# ADC-ADC.net
KiCad netlist of a schematic drawn in Altium Designer
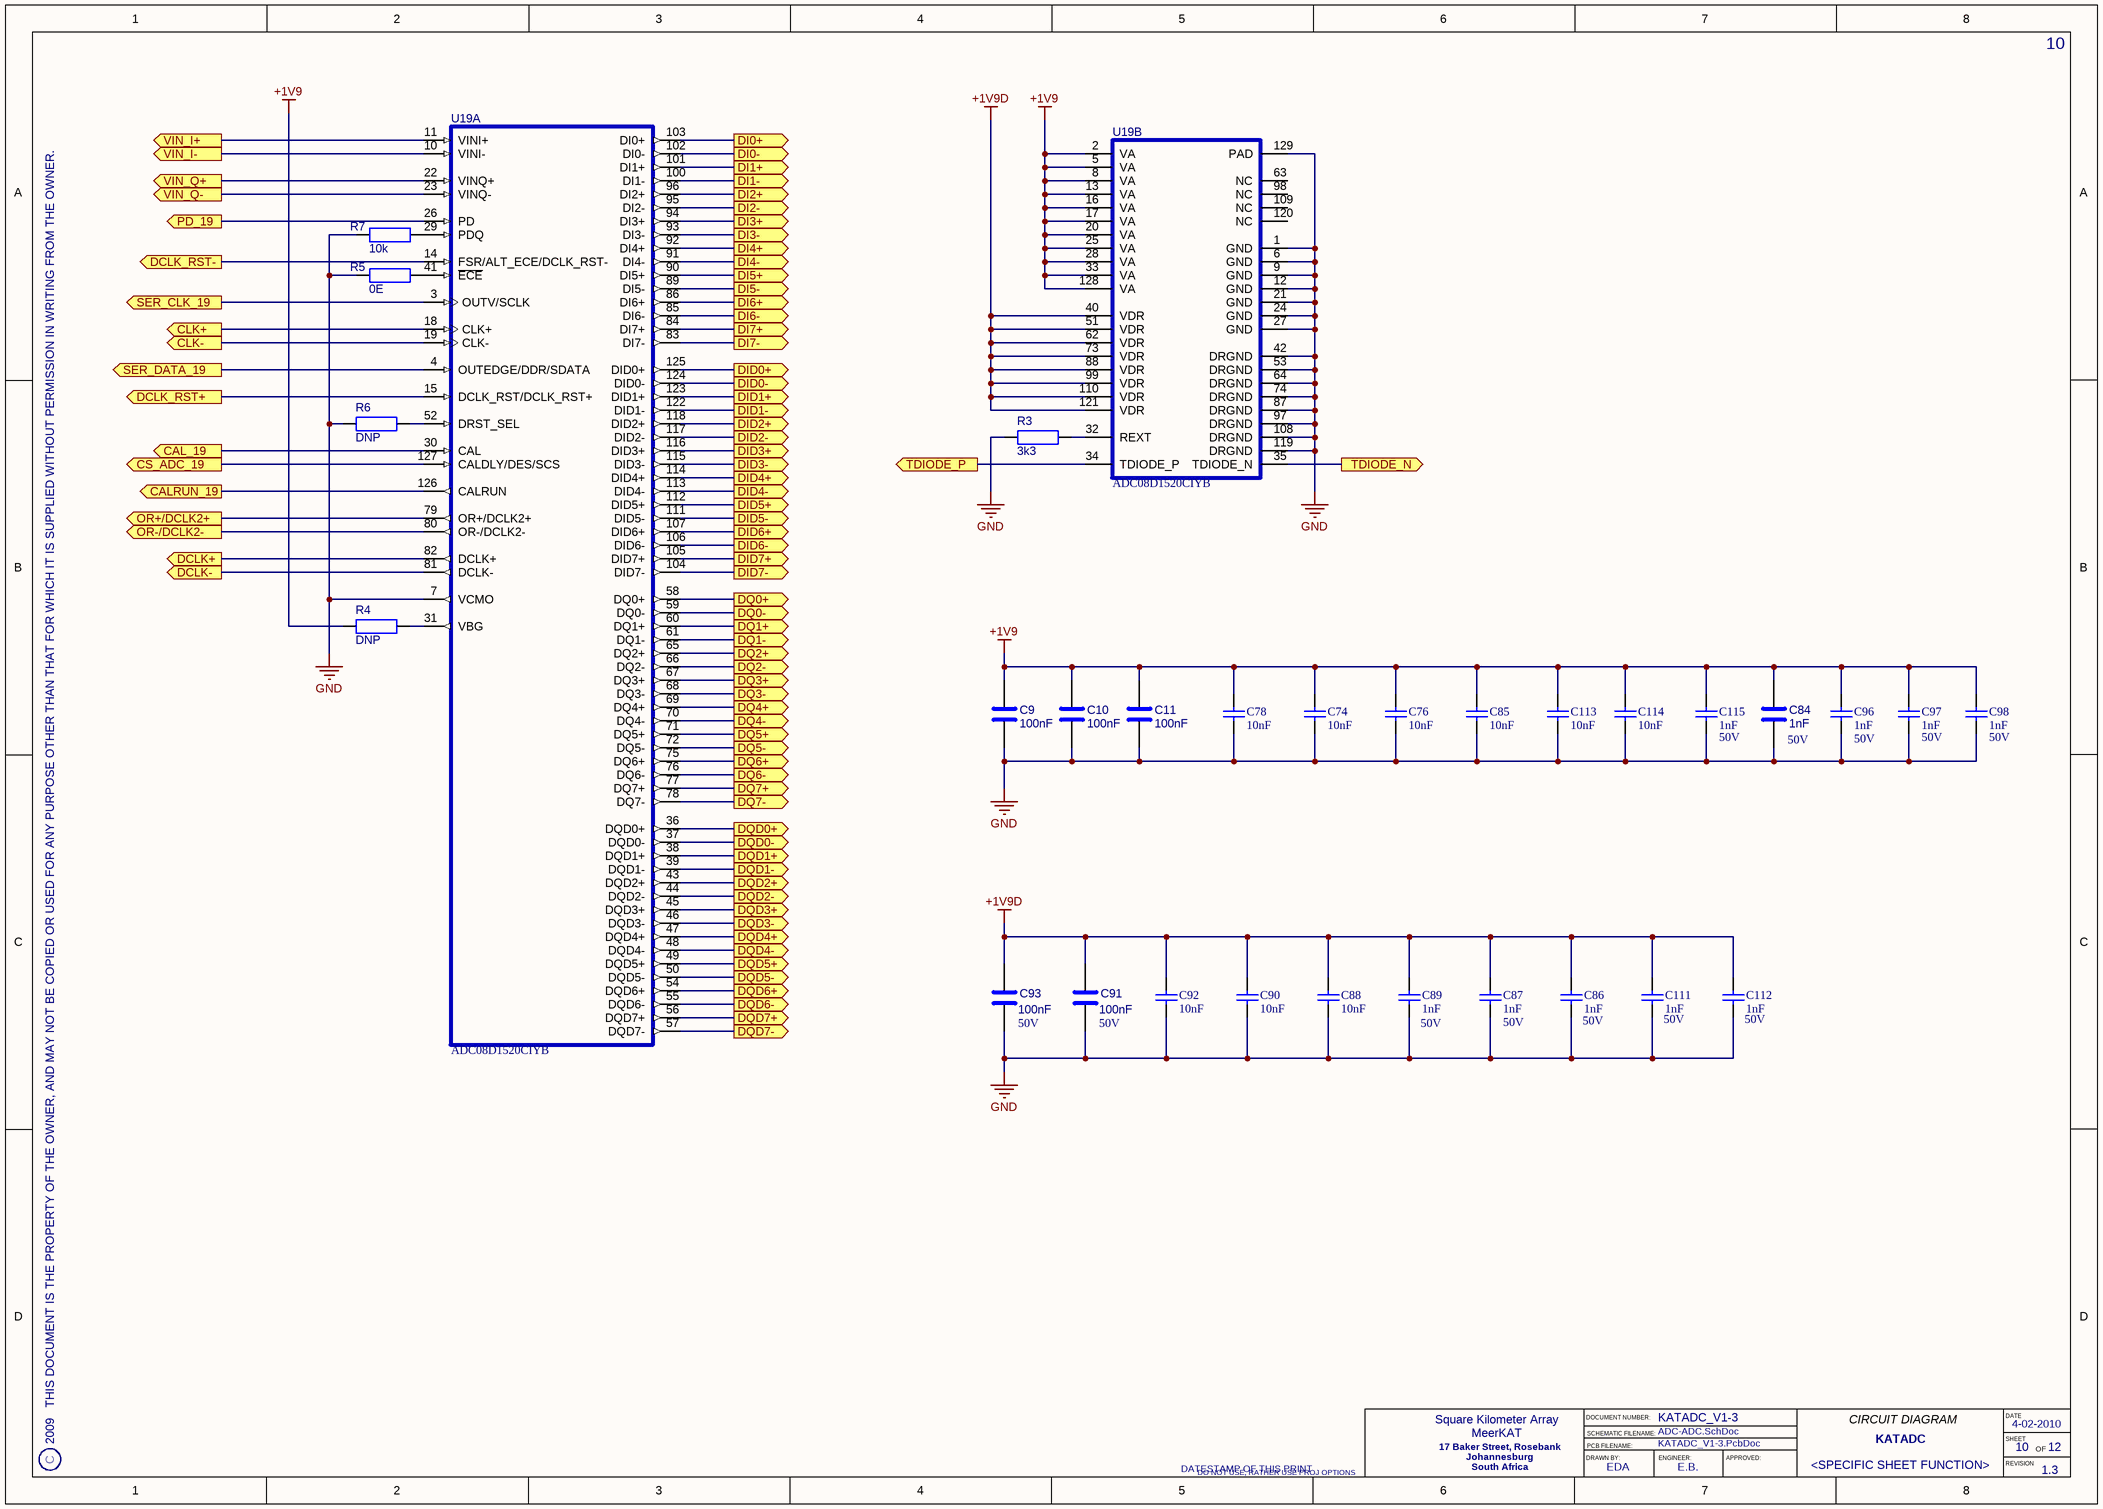
[diagram p0: ADC-ADC.SchDoc]

(export (version "E")
  (design (tool "Eeschema 10.0.6"))
  (components
    (comp (ref "C9")
      (value "100nF")
      (footprint "0603")
      (description "CAP SMD 0603")
      (fields (field (name "CREATED_BY") "*") (field (name "CHECKED_BY") "*"))
      (libsource (lib "Abdus-TEMP") (part "CAP-0603"))
    )
    (comp (ref "C10")
      (value "100nF")
      (footprint "0603")
      (description "CAP SMD 0603")
      (fields (field (name "CREATED_BY") "*") (field (name "CHECKED_BY") "*"))
      (libsource (lib "Abdus-TEMP") (part "CAP-0603"))
    )
    (comp (ref "C11")
      (value "100nF")
      (footprint "0603")
      (description "CAP SMD 0603")
      (fields (field (name "CREATED_BY") "*") (field (name "CHECKED_BY") "*"))
      (libsource (lib "Abdus-TEMP") (part "CAP-0603"))
    )
    (comp (ref "C74")
      (value "10nF")
      (footprint "CAPC1005X55N")
      (description "Capacitor 0402 SMD")
      (fields (field (name "CREATED_BY") "EDA-ASA") (field (name "CHECKED_BY") "*"))
      (libsource (lib "EDA-Passive") (part "cap0402"))
    )
    (comp (ref "C76")
      (value "10nF")
      (footprint "CAPC1005X55N")
      (description "Capacitor 0402 SMD")
      (fields (field (name "CREATED_BY") "EDA-ASA") (field (name "CHECKED_BY") "*"))
      (libsource (lib "EDA-Passive") (part "cap0402"))
    )
    (comp (ref "C78")
      (value "10nF")
      (footprint "CAPC1005X55N")
      (description "Capacitor 0402 SMD")
      (fields (field (name "CREATED_BY") "EDA-ASA") (field (name "CHECKED_BY") "*"))
      (libsource (lib "EDA-Passive") (part "cap0402"))
    )
    (comp (ref "C84")
      (value "1nF")
      (footprint "CAPC1005X55N")
      (description "CAP SMD 0603")
      (fields (field (name "VOLTAGE") "50V") (field (name "CREATED_BY") "*") (field (name "CHECKED_BY") "*"))
      (libsource (lib "Abdus-TEMP") (part "CAP-0603"))
    )
    (comp (ref "C85")
      (value "10nF")
      (footprint "CAPC1005X55N")
      (description "Capacitor 0402 SMD")
      (fields (field (name "CREATED_BY") "EDA-ASA") (field (name "CHECKED_BY") "*"))
      (libsource (lib "EDA-Passive") (part "cap0402"))
    )
    (comp (ref "C86")
      (value "1nF")
      (footprint "CAPC1005X55N")
      (description "Capacitor 0402 SMD")
      (fields
        (field (name "VOLTAGE") "50V")
        (field (name "CREATED_BY") "EDA-ASA")
        (field (name "CHECKED_BY") "*")
      )
      (libsource (lib "EDA-Passive") (part "cap0402"))
    )
    (comp (ref "C87")
      (value "1nF")
      (footprint "CAPC1005X55N")
      (description "Capacitor 0402 SMD")
      (fields
        (field (name "VOLTAGE") "50V")
        (field (name "CREATED_BY") "EDA-ASA")
        (field (name "CHECKED_BY") "*")
      )
      (libsource (lib "EDA-Passive") (part "cap0402"))
    )
    (comp (ref "C88")
      (value "10nF")
      (footprint "CAPC1005X55N")
      (description "Capacitor 0402 SMD")
      (fields (field (name "CREATED_BY") "EDA-ASA") (field (name "CHECKED_BY") "*"))
      (libsource (lib "EDA-Passive") (part "cap0402"))
    )
    (comp (ref "C89")
      (value "1nF")
      (footprint "CAPC1005X55N")
      (description "Capacitor 0402 SMD")
      (fields
        (field (name "VOLTAGE") "50V")
        (field (name "CREATED_BY") "EDA-ASA")
        (field (name "CHECKED_BY") "*")
      )
      (libsource (lib "EDA-Passive") (part "cap0402"))
    )
    (comp (ref "C90")
      (value "10nF")
      (footprint "CAPC1005X55N")
      (description "Capacitor 0402 SMD")
      (fields (field (name "CREATED_BY") "EDA-ASA") (field (name "CHECKED_BY") "*"))
      (libsource (lib "EDA-Passive") (part "cap0402"))
    )
    (comp (ref "C91")
      (value "100nF")
      (footprint "0603")
      (description "CAP SMD 0603")
      (fields (field (name "VOLTAGE") "50V") (field (name "CREATED_BY") "*") (field (name "CHECKED_BY") "*"))
      (libsource (lib "Abdus-TEMP") (part "CAP-0603"))
    )
    (comp (ref "C92")
      (value "10nF")
      (footprint "CAPC1005X55N")
      (description "Capacitor 0402 SMD")
      (fields (field (name "CREATED_BY") "EDA-ASA") (field (name "CHECKED_BY") "*"))
      (libsource (lib "EDA-Passive") (part "cap0402"))
    )
    (comp (ref "C93")
      (value "100nF")
      (footprint "0603")
      (description "CAP SMD 0603")
      (fields (field (name "VOLTAGE") "50V") (field (name "CREATED_BY") "*") (field (name "CHECKED_BY") "*"))
      (libsource (lib "Abdus-TEMP") (part "CAP-0603"))
    )
    (comp (ref "C96")
      (value "1nF")
      (footprint "CAPC1005X55N")
      (description "Capacitor 0402 SMD")
      (fields
        (field (name "VOLTAGE") "50V")
        (field (name "CREATED_BY") "EDA-ASA")
        (field (name "CHECKED_BY") "*")
      )
      (libsource (lib "EDA-Passive") (part "cap0402"))
    )
    (comp (ref "C97")
      (value "1nF")
      (footprint "CAPC1005X55N")
      (description "Capacitor 0402 SMD")
      (fields
        (field (name "VOLTAGE") "50V")
        (field (name "CREATED_BY") "EDA-ASA")
        (field (name "CHECKED_BY") "*")
      )
      (libsource (lib "EDA-Passive") (part "cap0402"))
    )
    (comp (ref "C98")
      (value "1nF")
      (footprint "CAPC1005X55N")
      (description "Capacitor 0402 SMD")
      (fields
        (field (name "VOLTAGE") "50V")
        (field (name "CREATED_BY") "EDA-ASA")
        (field (name "CHECKED_BY") "*")
      )
      (libsource (lib "EDA-Passive") (part "cap0402"))
    )
    (comp (ref "C111")
      (value "1nF")
      (footprint "CAPC1005X55N")
      (description "Capacitor 0402 SMD")
      (fields
        (field (name "VOLTAGE") "50V")
        (field (name "CREATED_BY") "EDA-ASA")
        (field (name "CHECKED_BY") "*")
      )
      (libsource (lib "EDA-Passive") (part "cap0402"))
    )
    (comp (ref "C112")
      (value "1nF")
      (footprint "CAPC1005X55N")
      (description "Capacitor 0402 SMD")
      (fields
        (field (name "VOLTAGE") "50V")
        (field (name "CREATED_BY") "EDA-ASA")
        (field (name "CHECKED_BY") "*")
      )
      (libsource (lib "EDA-Passive") (part "cap0402"))
    )
    (comp (ref "C113")
      (value "10nF")
      (footprint "CAPC1005X55N")
      (description "Capacitor 0402 SMD")
      (fields (field (name "CREATED_BY") "EDA-ASA") (field (name "CHECKED_BY") "*"))
      (libsource (lib "EDA-Passive") (part "cap0402"))
    )
    (comp (ref "C114")
      (value "10nF")
      (footprint "CAPC1005X55N")
      (description "Capacitor 0402 SMD")
      (fields (field (name "CREATED_BY") "EDA-ASA") (field (name "CHECKED_BY") "*"))
      (libsource (lib "EDA-Passive") (part "cap0402"))
    )
    (comp (ref "C115")
      (value "1nF")
      (footprint "CAPC1005X55N")
      (description "Capacitor 0402 SMD")
      (fields
        (field (name "VOLTAGE") "50V")
        (field (name "CREATED_BY") "EDA-ASA")
        (field (name "CHECKED_BY") "*")
      )
      (libsource (lib "EDA-Passive") (part "cap0402"))
    )
    (comp (ref "R3")
      (value "3k3")
      (footprint "RESC1005X40N")
      (description "RESISTOR SMD 0805")
      (fields (field (name "CREATED_BY") "*") (field (name "CHECKED_BY") "NN"))
      (libsource (lib "EDA_Passive") (part "RES-0805"))
    )
    (comp (ref "R4")
      (value "DNP")
      (footprint "RESC1005X40N")
      (description "RESISTOR SMD 0805")
      (fields (field (name "CREATED_BY") "*") (field (name "CHECKED_BY") "NN"))
      (libsource (lib "EDA_Passive") (part "RES-0805"))
    )
    (comp (ref "R5")
      (value "0E")
      (footprint "RESC1005X40N")
      (description "RESISTOR SMD 0805")
      (fields (field (name "CREATED_BY") "*") (field (name "CHECKED_BY") "NN"))
      (libsource (lib "EDA_Passive") (part "RES-0805"))
    )
    (comp (ref "R6")
      (value "DNP")
      (footprint "RESC1005X40N")
      (description "RESISTOR SMD 0805")
      (fields (field (name "CREATED_BY") "*") (field (name "CHECKED_BY") "NN"))
      (libsource (lib "EDA_Passive") (part "RES-0805"))
    )
    (comp (ref "R7")
      (value "10k")
      (footprint "RESC1005X40N")
      (description "RESISTOR SMD 0805")
      (fields (field (name "CREATED_BY") "*") (field (name "CHECKED_BY") "NN"))
      (libsource (lib "EDA_Passive") (part "RES-0805"))
    )
    (comp (ref "U19")
      (value "ADC08D1520CIYB")
      (footprint "NS_VNX128A")
      (description "Low Power, 8-Bit, Dual 1.5 GSPS or Single 3.0 GSPS A/D Converter")
      (fields
        (field (name "MANUFACTURER") "National Semiconductor")
        (field (name "CREATED_BY") "IN")
        (field (name "CHECKED_BY") "*")
      )
      (libsource (lib "Ishvah-TEMP") (part "ADC08D1520CIYB"))
    )
  )
  (nets
    (net (code "1") (name "+1V9") (class "Default")
      (node (ref "C10") (pin "2") (pinfunction "2_2") (pintype "passive"))
      (node (ref "C11") (pin "2") (pinfunction "2_2") (pintype "passive"))
      (node (ref "C113") (pin "1") (pinfunction "1_1") (pintype "passive"))
      (node (ref "C114") (pin "1") (pinfunction "1_1") (pintype "passive"))
      (node (ref "C115") (pin "1") (pinfunction "1_1") (pintype "passive"))
      (node (ref "C74") (pin "1") (pinfunction "1_1") (pintype "passive"))
      (node (ref "C76") (pin "1") (pinfunction "1_1") (pintype "passive"))
      (node (ref "C78") (pin "1") (pinfunction "1_1") (pintype "passive"))
      (node (ref "C84") (pin "1") (pinfunction "1_1") (pintype "passive"))
      (node (ref "C85") (pin "1") (pinfunction "1_1") (pintype "passive"))
      (node (ref "C9") (pin "2") (pinfunction "2_2") (pintype "passive"))
      (node (ref "C96") (pin "1") (pinfunction "1_1") (pintype "passive"))
      (node (ref "C97") (pin "1") (pinfunction "1_1") (pintype "passive"))
      (node (ref "C98") (pin "1") (pinfunction "1_1") (pintype "passive"))
      (node (ref "R4") (pin "1") (pinfunction "1_1") (pintype "passive"))
      (node (ref "U19") (pin "128") (pinfunction "VA_128") (pintype "power_in"))
      (node (ref "U19") (pin "13") (pinfunction "VA_13") (pintype "power_in"))
      (node (ref "U19") (pin "16") (pinfunction "VA_16") (pintype "power_in"))
      (node (ref "U19") (pin "17") (pinfunction "VA_17") (pintype "power_in"))
      (node (ref "U19") (pin "2") (pinfunction "VA_2") (pintype "power_in"))
      (node (ref "U19") (pin "20") (pinfunction "VA_20") (pintype "power_in"))
      (node (ref "U19") (pin "25") (pinfunction "VA_25") (pintype "power_in"))
      (node (ref "U19") (pin "28") (pinfunction "VA_28") (pintype "power_in"))
      (node (ref "U19") (pin "33") (pinfunction "VA_33") (pintype "power_in"))
      (node (ref "U19") (pin "5") (pinfunction "VA_5") (pintype "power_in"))
      (node (ref "U19") (pin "8") (pinfunction "VA_8") (pintype "power_in"))
    )
    (net (code "2") (name "+1V9D") (class "Default")
      (node (ref "C111") (pin "1") (pinfunction "1_1") (pintype "passive"))
      (node (ref "C112") (pin "1") (pinfunction "1_1") (pintype "passive"))
      (node (ref "C86") (pin "1") (pinfunction "1_1") (pintype "passive"))
      (node (ref "C87") (pin "1") (pinfunction "1_1") (pintype "passive"))
      (node (ref "C88") (pin "1") (pinfunction "1_1") (pintype "passive"))
      (node (ref "C89") (pin "1") (pinfunction "1_1") (pintype "passive"))
      (node (ref "C90") (pin "1") (pinfunction "1_1") (pintype "passive"))
      (node (ref "C91") (pin "1") (pinfunction "1_1") (pintype "passive"))
      (node (ref "C92") (pin "1") (pinfunction "1_1") (pintype "passive"))
      (node (ref "C93") (pin "1") (pinfunction "1_1") (pintype "passive"))
      (node (ref "U19") (pin "110") (pinfunction "VDR_110") (pintype "power_in"))
      (node (ref "U19") (pin "121") (pinfunction "VDR_121") (pintype "power_in"))
      (node (ref "U19") (pin "40") (pinfunction "VDR_40") (pintype "power_in"))
      (node (ref "U19") (pin "51") (pinfunction "VDR_51") (pintype "power_in"))
      (node (ref "U19") (pin "62") (pinfunction "VDR_62") (pintype "power_in"))
      (node (ref "U19") (pin "73") (pinfunction "VDR_73") (pintype "power_in"))
      (node (ref "U19") (pin "88") (pinfunction "VDR_88") (pintype "power_in"))
      (node (ref "U19") (pin "99") (pinfunction "VDR_99") (pintype "power_in"))
    )
    (net (code "3") (name "/CALRUN_19") (class "Default")
      (node (ref "U19") (pin "126") (pinfunction "CALRUN_126") (pintype "output"))
    )
    (net (code "4") (name "/CAL_19") (class "Default")
      (node (ref "U19") (pin "30") (pinfunction "CAL_30") (pintype "input"))
    )
    (net (code "5") (name "/CLK+") (class "Default")
      (node (ref "U19") (pin "18") (pinfunction "CLK+_18") (pintype "input"))
    )
    (net (code "6") (name "/CLK-") (class "Default")
      (node (ref "U19") (pin "19") (pinfunction "CLK-_19") (pintype "input"))
    )
    (net (code "7") (name "/CS_ADC_19") (class "Default")
      (node (ref "U19") (pin "127") (pinfunction "CALDLY/DES/SCS_127") (pintype "input"))
    )
    (net (code "8") (name "/DCLK+") (class "Default")
      (node (ref "U19") (pin "82") (pinfunction "DCLK+_82") (pintype "output"))
    )
    (net (code "9") (name "/DCLK-") (class "Default")
      (node (ref "U19") (pin "81") (pinfunction "DCLK-_81") (pintype "output"))
    )
    (net (code "10") (name "/DCLK_RST+") (class "Default")
      (node (ref "U19") (pin "15") (pinfunction "DCLK_RST/DCLK_RST+_15") (pintype "input"))
    )
    (net (code "11") (name "/DCLK_RST-") (class "Default")
      (node (ref "U19") (pin "14") (pinfunction "FSR/ALT_ECE/DCLK_RST-_14") (pintype "input"))
    )
    (net (code "12") (name "/DI0+") (class "Default")
      (node (ref "U19") (pin "103") (pinfunction "DI0+_103") (pintype "output"))
    )
    (net (code "13") (name "/DI0-") (class "Default")
      (node (ref "U19") (pin "102") (pinfunction "DI0-_102") (pintype "output"))
    )
    (net (code "14") (name "/DI1+") (class "Default")
      (node (ref "U19") (pin "101") (pinfunction "DI1+_101") (pintype "output"))
    )
    (net (code "15") (name "/DI1-") (class "Default")
      (node (ref "U19") (pin "100") (pinfunction "DI1-_100") (pintype "output"))
    )
    (net (code "16") (name "/DI2+") (class "Default")
      (node (ref "U19") (pin "96") (pinfunction "DI2+_96") (pintype "output"))
    )
    (net (code "17") (name "/DI2-") (class "Default")
      (node (ref "U19") (pin "95") (pinfunction "DI2-_95") (pintype "output"))
    )
    (net (code "18") (name "/DI3+") (class "Default")
      (node (ref "U19") (pin "94") (pinfunction "DI3+_94") (pintype "output"))
    )
    (net (code "19") (name "/DI3-") (class "Default")
      (node (ref "U19") (pin "93") (pinfunction "DI3-_93") (pintype "output"))
    )
    (net (code "20") (name "/DI4+") (class "Default")
      (node (ref "U19") (pin "92") (pinfunction "DI4+_92") (pintype "output"))
    )
    (net (code "21") (name "/DI4-") (class "Default")
      (node (ref "U19") (pin "91") (pinfunction "DI4-_91") (pintype "output"))
    )
    (net (code "22") (name "/DI5+") (class "Default")
      (node (ref "U19") (pin "90") (pinfunction "DI5+_90") (pintype "output"))
    )
    (net (code "23") (name "/DI5-") (class "Default")
      (node (ref "U19") (pin "89") (pinfunction "DI5-_89") (pintype "output"))
    )
    (net (code "24") (name "/DI6+") (class "Default")
      (node (ref "U19") (pin "86") (pinfunction "DI6+_86") (pintype "output"))
    )
    (net (code "25") (name "/DI6-") (class "Default")
      (node (ref "U19") (pin "85") (pinfunction "DI6-_85") (pintype "output"))
    )
    (net (code "26") (name "/DI7+") (class "Default")
      (node (ref "U19") (pin "84") (pinfunction "DI7+_84") (pintype "output"))
    )
    (net (code "27") (name "/DI7-") (class "Default")
      (node (ref "U19") (pin "83") (pinfunction "DI7-_83") (pintype "output"))
    )
    (net (code "28") (name "/DID0+") (class "Default")
      (node (ref "U19") (pin "125") (pinfunction "DID0+_125") (pintype "output"))
    )
    (net (code "29") (name "/DID0-") (class "Default")
      (node (ref "U19") (pin "124") (pinfunction "DID0-_124") (pintype "output"))
    )
    (net (code "30") (name "/DID1+") (class "Default")
      (node (ref "U19") (pin "123") (pinfunction "DID1+_123") (pintype "output"))
    )
    (net (code "31") (name "/DID1-") (class "Default")
      (node (ref "U19") (pin "122") (pinfunction "DID1-_122") (pintype "output"))
    )
    (net (code "32") (name "/DID2+") (class "Default")
      (node (ref "U19") (pin "118") (pinfunction "DID2+_118") (pintype "output"))
    )
    (net (code "33") (name "/DID2-") (class "Default")
      (node (ref "U19") (pin "117") (pinfunction "DID2-_117") (pintype "output"))
    )
    (net (code "34") (name "/DID3+") (class "Default")
      (node (ref "U19") (pin "116") (pinfunction "DID3+_116") (pintype "output"))
    )
    (net (code "35") (name "/DID3-") (class "Default")
      (node (ref "U19") (pin "115") (pinfunction "DID3-_115") (pintype "output"))
    )
    (net (code "36") (name "/DID4+") (class "Default")
      (node (ref "U19") (pin "114") (pinfunction "DID4+_114") (pintype "output"))
    )
    (net (code "37") (name "/DID4-") (class "Default")
      (node (ref "U19") (pin "113") (pinfunction "DID4-_113") (pintype "output"))
    )
    (net (code "38") (name "/DID5+") (class "Default")
      (node (ref "U19") (pin "112") (pinfunction "DID5+_112") (pintype "output"))
    )
    (net (code "39") (name "/DID5-") (class "Default")
      (node (ref "U19") (pin "111") (pinfunction "DID5-_111") (pintype "output"))
    )
    (net (code "40") (name "/DID6+") (class "Default")
      (node (ref "U19") (pin "107") (pinfunction "DID6+_107") (pintype "output"))
    )
    (net (code "41") (name "/DID6-") (class "Default")
      (node (ref "U19") (pin "106") (pinfunction "DID6-_106") (pintype "output"))
    )
    (net (code "42") (name "/DID7+") (class "Default")
      (node (ref "U19") (pin "105") (pinfunction "DID7+_105") (pintype "output"))
    )
    (net (code "43") (name "/DID7-") (class "Default")
      (node (ref "U19") (pin "104") (pinfunction "DID7-_104") (pintype "output"))
    )
    (net (code "44") (name "/DQ0+") (class "Default")
      (node (ref "U19") (pin "58") (pinfunction "DQ0+_58") (pintype "output"))
    )
    (net (code "45") (name "/DQ0-") (class "Default")
      (node (ref "U19") (pin "59") (pinfunction "DQ0-_59") (pintype "output"))
    )
    (net (code "46") (name "/DQ1+") (class "Default")
      (node (ref "U19") (pin "60") (pinfunction "DQ1+_60") (pintype "output"))
    )
    (net (code "47") (name "/DQ1-") (class "Default")
      (node (ref "U19") (pin "61") (pinfunction "DQ1-_61") (pintype "output"))
    )
    (net (code "48") (name "/DQ2+") (class "Default")
      (node (ref "U19") (pin "65") (pinfunction "DQ2+_65") (pintype "output"))
    )
    (net (code "49") (name "/DQ2-") (class "Default")
      (node (ref "U19") (pin "66") (pinfunction "DQ2-_66") (pintype "output"))
    )
    (net (code "50") (name "/DQ3+") (class "Default")
      (node (ref "U19") (pin "67") (pinfunction "DQ3+_67") (pintype "output"))
    )
    (net (code "51") (name "/DQ3-") (class "Default")
      (node (ref "U19") (pin "68") (pinfunction "DQ3-_68") (pintype "output"))
    )
    (net (code "52") (name "/DQ4+") (class "Default")
      (node (ref "U19") (pin "69") (pinfunction "DQ4+_69") (pintype "output"))
    )
    (net (code "53") (name "/DQ4-") (class "Default")
      (node (ref "U19") (pin "70") (pinfunction "DQ4-_70") (pintype "output"))
    )
    (net (code "54") (name "/DQ5+") (class "Default")
      (node (ref "U19") (pin "71") (pinfunction "DQ5+_71") (pintype "output"))
    )
    (net (code "55") (name "/DQ5-") (class "Default")
      (node (ref "U19") (pin "72") (pinfunction "DQ5-_72") (pintype "output"))
    )
    (net (code "56") (name "/DQ6+") (class "Default")
      (node (ref "U19") (pin "75") (pinfunction "DQ6+_75") (pintype "output"))
    )
    (net (code "57") (name "/DQ6-") (class "Default")
      (node (ref "U19") (pin "76") (pinfunction "DQ6-_76") (pintype "output"))
    )
    (net (code "58") (name "/DQ7+") (class "Default")
      (node (ref "U19") (pin "77") (pinfunction "DQ7+_77") (pintype "output"))
    )
    (net (code "59") (name "/DQ7-") (class "Default")
      (node (ref "U19") (pin "78") (pinfunction "DQ7-_78") (pintype "output"))
    )
    (net (code "60") (name "/DQD0+") (class "Default")
      (node (ref "U19") (pin "36") (pinfunction "DQD0+_36") (pintype "output"))
    )
    (net (code "61") (name "/DQD0-") (class "Default")
      (node (ref "U19") (pin "37") (pinfunction "DQD0-_37") (pintype "output"))
    )
    (net (code "62") (name "/DQD1+") (class "Default")
      (node (ref "U19") (pin "38") (pinfunction "DQD1+_38") (pintype "output"))
    )
    (net (code "63") (name "/DQD1-") (class "Default")
      (node (ref "U19") (pin "39") (pinfunction "DQD1-_39") (pintype "output"))
    )
    (net (code "64") (name "/DQD2+") (class "Default")
      (node (ref "U19") (pin "43") (pinfunction "DQD2+_43") (pintype "output"))
    )
    (net (code "65") (name "/DQD2-") (class "Default")
      (node (ref "U19") (pin "44") (pinfunction "DQD2-_44") (pintype "output"))
    )
    (net (code "66") (name "/DQD3+") (class "Default")
      (node (ref "U19") (pin "45") (pinfunction "DQD3+_45") (pintype "output"))
    )
    (net (code "67") (name "/DQD3-") (class "Default")
      (node (ref "U19") (pin "46") (pinfunction "DQD3-_46") (pintype "output"))
    )
    (net (code "68") (name "/DQD4+") (class "Default")
      (node (ref "U19") (pin "47") (pinfunction "DQD4+_47") (pintype "output"))
    )
    (net (code "69") (name "/DQD4-") (class "Default")
      (node (ref "U19") (pin "48") (pinfunction "DQD4-_48") (pintype "output"))
    )
    (net (code "70") (name "/DQD5+") (class "Default")
      (node (ref "U19") (pin "49") (pinfunction "DQD5+_49") (pintype "output"))
    )
    (net (code "71") (name "/DQD5-") (class "Default")
      (node (ref "U19") (pin "50") (pinfunction "DQD5-_50") (pintype "output"))
    )
    (net (code "72") (name "/DQD6+") (class "Default")
      (node (ref "U19") (pin "54") (pinfunction "DQD6+_54") (pintype "output"))
    )
    (net (code "73") (name "/DQD6-") (class "Default")
      (node (ref "U19") (pin "55") (pinfunction "DQD6-_55") (pintype "output"))
    )
    (net (code "74") (name "/DQD7+") (class "Default")
      (node (ref "U19") (pin "56") (pinfunction "DQD7+_56") (pintype "output"))
    )
    (net (code "75") (name "/DQD7-") (class "Default")
      (node (ref "U19") (pin "57") (pinfunction "DQD7-_57") (pintype "output"))
    )
    (net (code "76") (name "/OR+{slash}DCLK2+") (class "Default")
      (node (ref "U19") (pin "79") (pinfunction "OR+/DCLK2+_79") (pintype "output"))
    )
    (net (code "77") (name "/OR-{slash}DCLK2-") (class "Default")
      (node (ref "U19") (pin "80") (pinfunction "OR-/DCLK2-_80") (pintype "output"))
    )
    (net (code "78") (name "/PD_19") (class "Default")
      (node (ref "U19") (pin "26") (pinfunction "PD_26") (pintype "input"))
    )
    (net (code "79") (name "/SER_CLK_19") (class "Default")
      (node (ref "U19") (pin "3") (pinfunction "OUTV/SCLK_3") (pintype "input"))
    )
    (net (code "80") (name "/SER_DATA_19") (class "Default")
      (node (ref "U19") (pin "4") (pinfunction "OUTEDGE/DDR/SDATA_4") (pintype "input"))
    )
    (net (code "81") (name "/TDIODE_N") (class "Default")
      (node (ref "U19") (pin "35") (pinfunction "TDIODE_N_35") (pintype "passive"))
    )
    (net (code "82") (name "/TDIODE_P") (class "Default")
      (node (ref "U19") (pin "34") (pinfunction "TDIODE_P_34") (pintype "passive"))
    )
    (net (code "83") (name "/VIN_I+") (class "Default")
      (node (ref "U19") (pin "11") (pinfunction "VINI+_11") (pintype "input"))
    )
    (net (code "84") (name "/VIN_I-") (class "Default")
      (node (ref "U19") (pin "10") (pinfunction "VINI-_10") (pintype "input"))
    )
    (net (code "85") (name "/VIN_Q+") (class "Default")
      (node (ref "U19") (pin "22") (pinfunction "VINQ+_22") (pintype "input"))
    )
    (net (code "86") (name "/VIN_Q-") (class "Default")
      (node (ref "U19") (pin "23") (pinfunction "VINQ-_23") (pintype "input"))
    )
    (net (code "87") (name "GND") (class "Default")
      (node (ref "C10") (pin "1") (pinfunction "1_1") (pintype "passive"))
      (node (ref "C11") (pin "1") (pinfunction "1_1") (pintype "passive"))
      (node (ref "C111") (pin "2") (pinfunction "2_2") (pintype "passive"))
      (node (ref "C112") (pin "2") (pinfunction "2_2") (pintype "passive"))
      (node (ref "C113") (pin "2") (pinfunction "2_2") (pintype "passive"))
      (node (ref "C114") (pin "2") (pinfunction "2_2") (pintype "passive"))
      (node (ref "C115") (pin "2") (pinfunction "2_2") (pintype "passive"))
      (node (ref "C74") (pin "2") (pinfunction "2_2") (pintype "passive"))
      (node (ref "C76") (pin "2") (pinfunction "2_2") (pintype "passive"))
      (node (ref "C78") (pin "2") (pinfunction "2_2") (pintype "passive"))
      (node (ref "C84") (pin "2") (pinfunction "2_2") (pintype "passive"))
      (node (ref "C85") (pin "2") (pinfunction "2_2") (pintype "passive"))
      (node (ref "C86") (pin "2") (pinfunction "2_2") (pintype "passive"))
      (node (ref "C87") (pin "2") (pinfunction "2_2") (pintype "passive"))
      (node (ref "C88") (pin "2") (pinfunction "2_2") (pintype "passive"))
      (node (ref "C89") (pin "2") (pinfunction "2_2") (pintype "passive"))
      (node (ref "C9") (pin "1") (pinfunction "1_1") (pintype "passive"))
      (node (ref "C90") (pin "2") (pinfunction "2_2") (pintype "passive"))
      (node (ref "C91") (pin "2") (pinfunction "2_2") (pintype "passive"))
      (node (ref "C92") (pin "2") (pinfunction "2_2") (pintype "passive"))
      (node (ref "C93") (pin "2") (pinfunction "2_2") (pintype "passive"))
      (node (ref "C96") (pin "2") (pinfunction "2_2") (pintype "passive"))
      (node (ref "C97") (pin "2") (pinfunction "2_2") (pintype "passive"))
      (node (ref "C98") (pin "2") (pinfunction "2_2") (pintype "passive"))
      (node (ref "R3") (pin "1") (pinfunction "1_1") (pintype "passive"))
      (node (ref "R5") (pin "1") (pinfunction "1_1") (pintype "passive"))
      (node (ref "R6") (pin "1") (pinfunction "1_1") (pintype "passive"))
      (node (ref "R7") (pin "1") (pinfunction "1_1") (pintype "passive"))
      (node (ref "U19") (pin "1") (pinfunction "GND_1") (pintype "power_in"))
      (node (ref "U19") (pin "108") (pinfunction "DRGND_108") (pintype "power_in"))
      (node (ref "U19") (pin "119") (pinfunction "DRGND_119") (pintype "power_in"))
      (node (ref "U19") (pin "12") (pinfunction "GND_12") (pintype "power_in"))
      (node (ref "U19") (pin "129") (pinfunction "PAD_129") (pintype "power_in"))
      (node (ref "U19") (pin "21") (pinfunction "GND_21") (pintype "power_in"))
      (node (ref "U19") (pin "24") (pinfunction "GND_24") (pintype "power_in"))
      (node (ref "U19") (pin "27") (pinfunction "GND_27") (pintype "power_in"))
      (node (ref "U19") (pin "42") (pinfunction "DRGND_42") (pintype "power_in"))
      (node (ref "U19") (pin "53") (pinfunction "DRGND_53") (pintype "power_in"))
      (node (ref "U19") (pin "6") (pinfunction "GND_6") (pintype "power_in"))
      (node (ref "U19") (pin "64") (pinfunction "DRGND_64") (pintype "power_in"))
      (node (ref "U19") (pin "7") (pinfunction "VCMO_7") (pintype "output"))
      (node (ref "U19") (pin "74") (pinfunction "DRGND_74") (pintype "power_in"))
      (node (ref "U19") (pin "87") (pinfunction "DRGND_87") (pintype "power_in"))
      (node (ref "U19") (pin "9") (pinfunction "GND_9") (pintype "power_in"))
      (node (ref "U19") (pin "97") (pinfunction "DRGND_97") (pintype "power_in"))
    )
    (net (code "88") (name "Net-(U19A-DRST_SEL)") (class "Default")
      (node (ref "R6") (pin "2") (pinfunction "2_2") (pintype "passive"))
      (node (ref "U19") (pin "52") (pinfunction "DRST_SEL_52") (pintype "input"))
    )
    (net (code "89") (name "Net-(U19A-PDQ)") (class "Default")
      (node (ref "R7") (pin "2") (pinfunction "2_2") (pintype "passive"))
      (node (ref "U19") (pin "29") (pinfunction "PDQ_29") (pintype "input"))
    )
    (net (code "90") (name "Net-(U19A-VBG)") (class "Default")
      (node (ref "R4") (pin "2") (pinfunction "2_2") (pintype "passive"))
      (node (ref "U19") (pin "31") (pinfunction "VBG_31") (pintype "output"))
    )
    (net (code "91") (name "Net-(U19A-~{ECE})") (class "Default")
      (node (ref "R5") (pin "2") (pinfunction "2_2") (pintype "passive"))
      (node (ref "U19") (pin "41") (pinfunction "~{ECE}_41") (pintype "input"))
    )
    (net (code "92") (name "Net-(U19B-REXT)") (class "Default")
      (node (ref "R3") (pin "2") (pinfunction "2_2") (pintype "passive"))
      (node (ref "U19") (pin "32") (pinfunction "REXT_32") (pintype "passive"))
    )
    (net (code "93") (name "unconnected-(U19B-NC-Pad63)") (class "Default")
      (node (ref "U19") (pin "63") (pinfunction "NC_63") (pintype "passive"))
    )
    (net (code "94") (name "unconnected-(U19B-NC-Pad98)") (class "Default")
      (node (ref "U19") (pin "98") (pinfunction "NC_98") (pintype "passive"))
    )
    (net (code "95") (name "unconnected-(U19B-NC-Pad109)") (class "Default")
      (node (ref "U19") (pin "109") (pinfunction "NC_109") (pintype "passive"))
    )
    (net (code "96") (name "unconnected-(U19B-NC-Pad120)") (class "Default")
      (node (ref "U19") (pin "120") (pinfunction "NC_120") (pintype "passive"))
    )
  )
)
